# tiny_tht_encoder_board.net
KiCad netlist of a schematic drawn in EAGLE
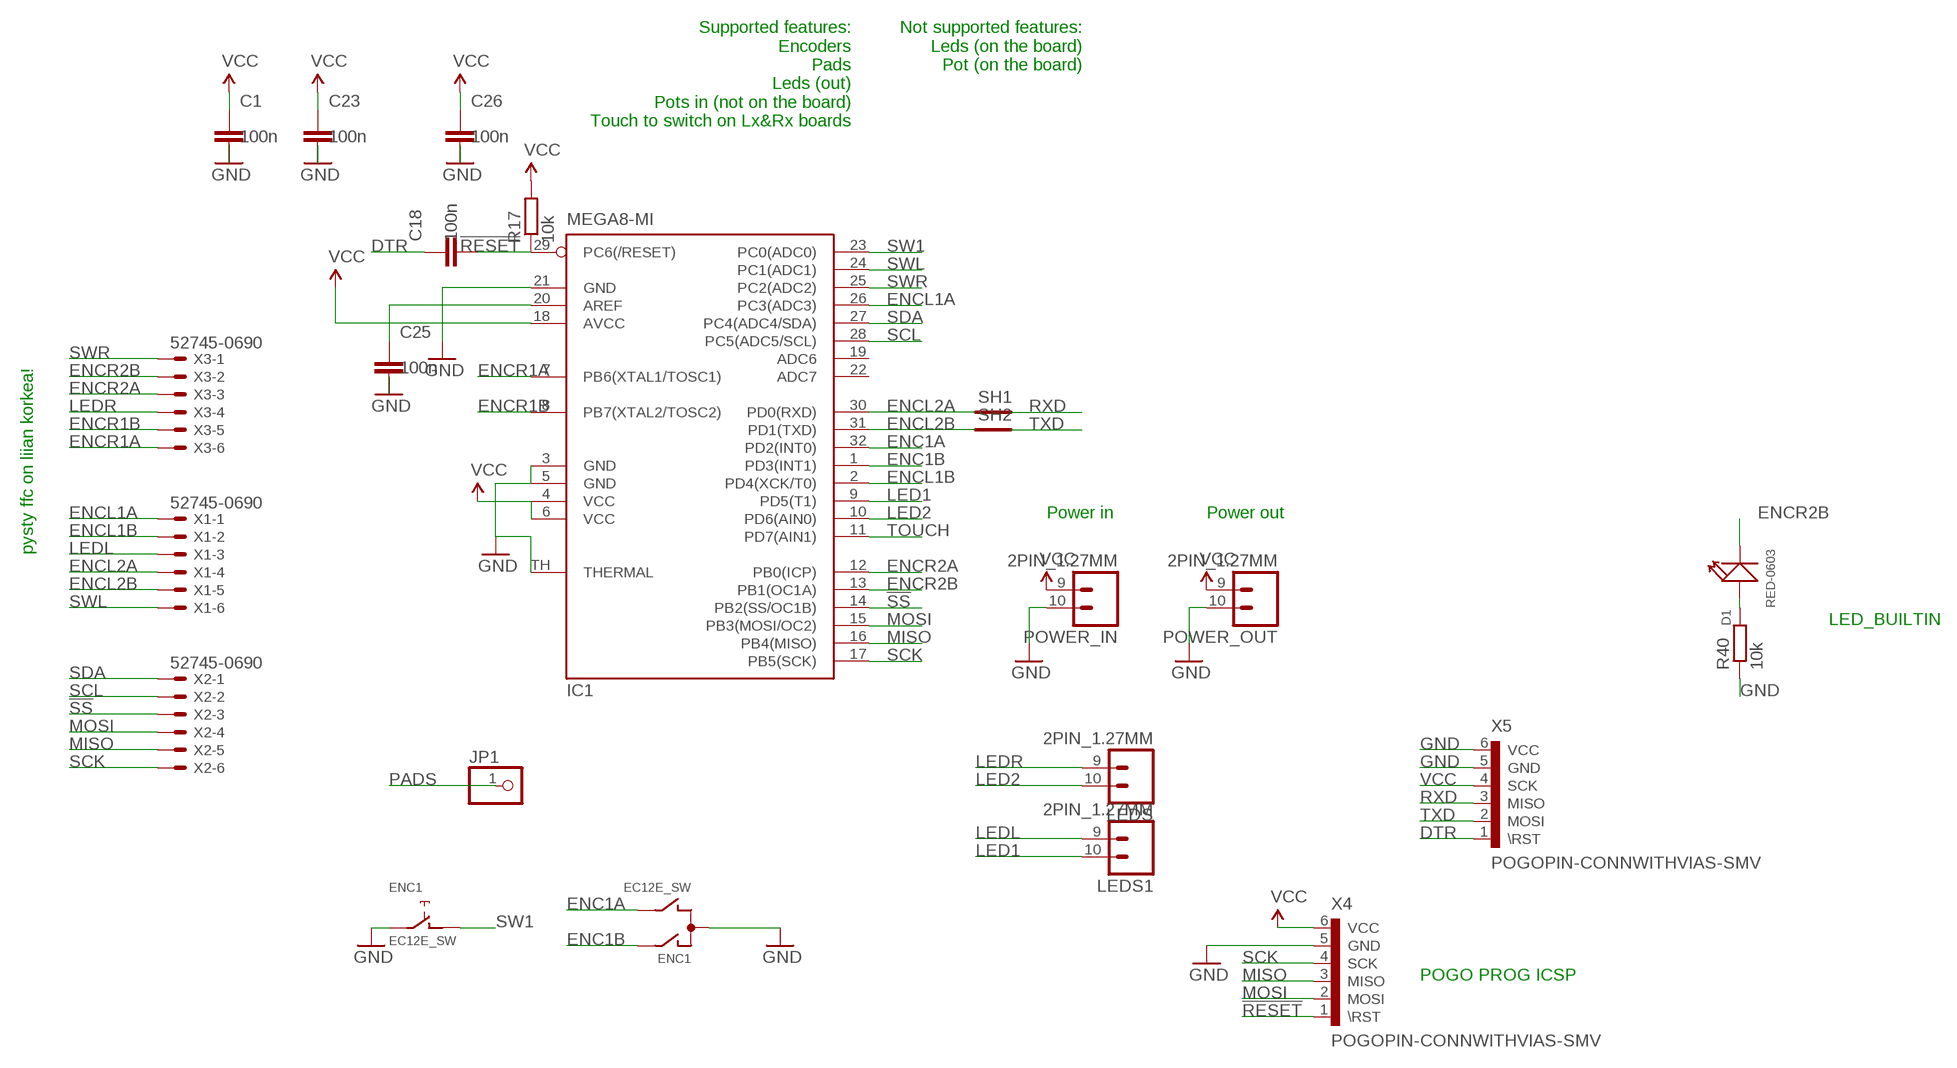
[diagram p0: schematic, sheet 1]
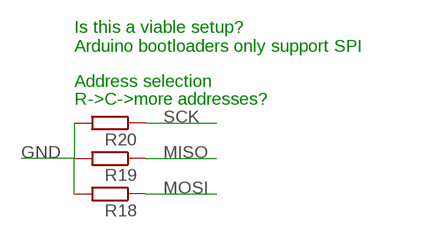
[diagram p1: schematic, sheet 2]
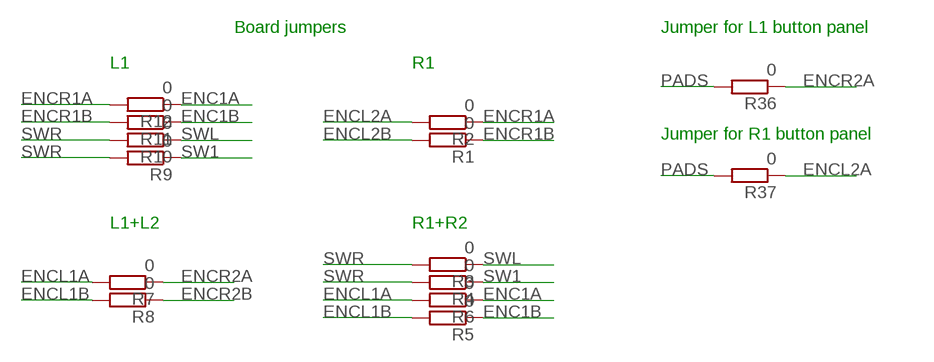
[diagram p2: schematic, sheet 3]

(export (version "E")
  (design (tool "Eeschema 10.0.6"))
  (components
    (comp (ref "R1")
      (value "0")
      (footprint "eagle-import:R0603")
      (fields (field (name "SPICEPREFIX") "R"))
      (libsource (lib "eagle-import") (part "R-EU_R0603"))
    )
    (comp (ref "R2")
      (value "0")
      (footprint "eagle-import:R0603")
      (fields (field (name "SPICEPREFIX") "R"))
      (libsource (lib "eagle-import") (part "R-EU_R0603"))
    )
    (comp (ref "R3")
      (value "0")
      (footprint "eagle-import:R0603")
      (fields (field (name "SPICEPREFIX") "R"))
      (libsource (lib "eagle-import") (part "R-EU_R0603"))
    )
    (comp (ref "R4")
      (value "0")
      (footprint "eagle-import:R0603")
      (fields (field (name "SPICEPREFIX") "R"))
      (libsource (lib "eagle-import") (part "R-EU_R0603"))
    )
    (comp (ref "R5")
      (value "0")
      (footprint "eagle-import:R0603")
      (fields (field (name "SPICEPREFIX") "R"))
      (libsource (lib "eagle-import") (part "R-EU_R0603"))
    )
    (comp (ref "R6")
      (value "0")
      (footprint "eagle-import:R0603")
      (fields (field (name "SPICEPREFIX") "R"))
      (libsource (lib "eagle-import") (part "R-EU_R0603"))
    )
    (comp (ref "R7")
      (value "0")
      (footprint "eagle-import:R0603")
      (fields (field (name "SPICEPREFIX") "R"))
      (libsource (lib "eagle-import") (part "R-EU_R0603"))
    )
    (comp (ref "R8")
      (value "0")
      (footprint "eagle-import:R0603")
      (fields (field (name "SPICEPREFIX") "R"))
      (libsource (lib "eagle-import") (part "R-EU_R0603"))
    )
    (comp (ref "R9")
      (value "0")
      (footprint "eagle-import:R0603")
      (fields (field (name "SPICEPREFIX") "R"))
      (libsource (lib "eagle-import") (part "R-EU_R0603"))
    )
    (comp (ref "R10")
      (value "0")
      (footprint "eagle-import:R0603")
      (fields (field (name "SPICEPREFIX") "R"))
      (libsource (lib "eagle-import") (part "R-EU_R0603"))
    )
    (comp (ref "R11")
      (value "0")
      (footprint "eagle-import:R0603")
      (fields (field (name "SPICEPREFIX") "R"))
      (libsource (lib "eagle-import") (part "R-EU_R0603"))
    )
    (comp (ref "R12")
      (value "0")
      (footprint "eagle-import:R0603")
      (fields (field (name "SPICEPREFIX") "R"))
      (libsource (lib "eagle-import") (part "R-EU_R0603"))
    )
    (comp (ref "R36")
      (value "0")
      (footprint "eagle-import:R0402")
      (fields (field (name "SPICEPREFIX") "R"))
      (libsource (lib "eagle-import") (part "rcl_334_R-EU_R0402"))
    )
    (comp (ref "R37")
      (value "0")
      (footprint "eagle-import:R0402")
      (fields (field (name "SPICEPREFIX") "R"))
      (libsource (lib "eagle-import") (part "rcl_334_R-EU_R0402"))
    )
    (comp (ref "C1")
      (value "100n")
      (footprint "eagle-import:C0402")
      (libsource (lib "eagle-import") (part "C-EUC0402"))
    )
    (comp (ref "C18")
      (value "100n")
      (footprint "eagle-import:C0402")
      (libsource (lib "eagle-import") (part "C-EUC0402"))
    )
    (comp (ref "C23")
      (value "100n")
      (footprint "eagle-import:C0402")
      (libsource (lib "eagle-import") (part "C-EUC0402"))
    )
    (comp (ref "C25")
      (value "100n")
      (footprint "eagle-import:C0402")
      (libsource (lib "eagle-import") (part "C-EUC0402"))
    )
    (comp (ref "C26")
      (value "100n")
      (footprint "eagle-import:C0402")
      (libsource (lib "eagle-import") (part "C-EUC0402"))
    )
    (comp (ref "D1")
      (value "RED-0603")
      (footprint "eagle-import:LED-0603")
      (fields (field (name "MPN") "19-217-R6C-AL1M2VY-3T"))
      (libsource (lib "eagle-import") (part "LED-SMD-RED-DIFFUSED(0603)"))
    )
    (comp (ref "ENC1")
      (value "EC12E_SW")
      (footprint "eagle-import:ALPS_EC12E_SW")
      (fields (field (name "MPN") "EC12E2424407"))
      (libsource (lib "eagle-import") (part "EC12E_SW"))
    )
    (comp (ref "IC1")
      (value "MEGA8-MI")
      (footprint "eagle-import:MLF32-TH")
      (fields (field (name "MPN") "ATMEGA88PA-MU"))
      (libsource (lib "eagle-import") (part "MEGA8-MI"))
    )
    (comp (ref "JP1")
      (value "PINHD-1X1")
      (footprint "eagle-import:1X01")
      (libsource (lib "eagle-import") (part "PINHD-1X1"))
    )
    (comp (ref "LEDS")
      (value "2PIN_1.27MM")
      (footprint "eagle-import:1X02_1.27MM_NO_SILK")
      (libsource (lib "eagle-import") (part "2PIN_1.27MM"))
    )
    (comp (ref "LEDS1")
      (value "2PIN_1.27MM")
      (footprint "eagle-import:1X02_1.27MM_NO_SILK")
      (libsource (lib "eagle-import") (part "2PIN_1.27MM"))
    )
    (comp (ref "POWER_IN")
      (value "2PIN_1.27MM")
      (footprint "eagle-import:1X02_1.27MM_NO_SILK")
      (libsource (lib "eagle-import") (part "2PIN_1.27MM"))
    )
    (comp (ref "POWER_OUT")
      (value "2PIN_1.27MM")
      (footprint "eagle-import:1X02_1.27MM_NO_SILK")
      (libsource (lib "eagle-import") (part "2PIN_1.27MM"))
    )
    (comp (ref "R17")
      (value "10k")
      (footprint "eagle-import:R0402")
      (libsource (lib "eagle-import") (part "rcl_334_R-EU_R0402"))
    )
    (comp (ref "R40")
      (value "10k")
      (footprint "eagle-import:R0402")
      (libsource (lib "eagle-import") (part "rcl_334_R-EU_R0402"))
    )
    (comp (ref "SH1")
      (value "SHORT")
      (footprint "eagle-import:SHORT_TOP_8MIL")
      (libsource (lib "eagle-import") (part "SHORT"))
    )
    (comp (ref "SH2")
      (value "SHORT")
      (footprint "eagle-import:SHORT_TOP_8MIL")
      (libsource (lib "eagle-import") (part "SHORT"))
    )
    (comp (ref "X1")
      (value "52745-0690")
      (footprint "eagle-import:52745-0690")
      (fields (field (name "MF") "MOLEX"))
      (libsource (lib "eagle-import") (part "52745-0690"))
    )
    (comp (ref "X2")
      (value "52745-0690")
      (footprint "eagle-import:52745-0690")
      (fields (field (name "MF") "MOLEX"))
      (libsource (lib "eagle-import") (part "52745-0690"))
    )
    (comp (ref "X3")
      (value "52745-0690")
      (footprint "eagle-import:52745-0690")
      (fields (field (name "MF") "MOLEX"))
      (libsource (lib "eagle-import") (part "52745-0690"))
    )
    (comp (ref "X4")
      (value "POGOPIN-CONNWITHVIAS-SMV")
      (footprint "eagle-import:POGOPROG-CONN-OH-SMALLERVIAS")
      (libsource (lib "eagle-import") (part "POGOPIN-CONNWITHVIAS-SMV"))
    )
    (comp (ref "X5")
      (value "POGOPIN-CONNWITHVIAS-SMV")
      (footprint "eagle-import:POGOPROG-CONN-OH-SMALLERVIAS")
      (libsource (lib "eagle-import") (part "POGOPIN-CONNWITHVIAS-SMV"))
    )
    (comp (ref "R18")
      (value "R-EU_R0402")
      (footprint "eagle-import:R0402")
      (libsource (lib "eagle-import") (part "rcl_334_R-EU_R0402"))
    )
    (comp (ref "R19")
      (value "R-EU_R0402")
      (footprint "eagle-import:R0402")
      (libsource (lib "eagle-import") (part "rcl_334_R-EU_R0402"))
    )
    (comp (ref "R20")
      (value "R-EU_R0402")
      (footprint "eagle-import:R0402")
      (libsource (lib "eagle-import") (part "rcl_334_R-EU_R0402"))
    )
  )
  (nets
    (net (code "1") (name "DTR") (class "Default")
      (node (ref "C18") (pin "1") (pinfunction "1_1") (pintype "passive"))
      (node (ref "X5") (pin "1") (pinfunction "\\RST_1") (pintype "bidirectional"))
    )
    (net (code "2") (name "ENC1A") (class "Default")
      (node (ref "ENC1") (pin "B") (pinfunction "B_B") (pintype "passive"))
      (node (ref "IC1") (pin "32") (pinfunction "PD2(INT0)_32") (pintype "bidirectional"))
      (node (ref "R12") (pin "1") (pinfunction "1_1") (pintype "passive"))
      (node (ref "R6") (pin "1") (pinfunction "1_1") (pintype "passive"))
    )
    (net (code "3") (name "ENC1B") (class "Default")
      (node (ref "ENC1") (pin "A") (pinfunction "A_A") (pintype "passive"))
      (node (ref "IC1") (pin "1") (pinfunction "PD3(INT1)_1") (pintype "bidirectional"))
      (node (ref "R11") (pin "1") (pinfunction "1_1") (pintype "passive"))
      (node (ref "R5") (pin "1") (pinfunction "1_1") (pintype "passive"))
    )
    (net (code "4") (name "ENCL1A") (class "Default")
      (node (ref "IC1") (pin "26") (pinfunction "PC3(ADC3)_26") (pintype "bidirectional"))
      (node (ref "R6") (pin "2") (pinfunction "2_2") (pintype "passive"))
      (node (ref "R7") (pin "2") (pinfunction "2_2") (pintype "passive"))
      (node (ref "X1") (pin "1") (pinfunction "S_1") (pintype "passive"))
    )
    (net (code "5") (name "ENCL1B") (class "Default")
      (node (ref "IC1") (pin "2") (pinfunction "PD4(XCK/T0)_2") (pintype "bidirectional"))
      (node (ref "R5") (pin "2") (pinfunction "2_2") (pintype "passive"))
      (node (ref "R8") (pin "2") (pinfunction "2_2") (pintype "passive"))
      (node (ref "X1") (pin "2") (pinfunction "S_2") (pintype "passive"))
    )
    (net (code "6") (name "ENCL2A") (class "Default")
      (node (ref "IC1") (pin "30") (pinfunction "PD0(RXD)_30") (pintype "bidirectional"))
      (node (ref "R2") (pin "2") (pinfunction "2_2") (pintype "passive"))
      (node (ref "R37") (pin "1") (pinfunction "1_1") (pintype "passive"))
      (node (ref "SH1") (pin "P$1") (pinfunction "P$1_P$1") (pintype "bidirectional"))
      (node (ref "X1") (pin "4") (pinfunction "S_4") (pintype "passive"))
    )
    (net (code "7") (name "ENCL2B") (class "Default")
      (node (ref "IC1") (pin "31") (pinfunction "PD1(TXD)_31") (pintype "bidirectional"))
      (node (ref "R1") (pin "2") (pinfunction "2_2") (pintype "passive"))
      (node (ref "SH2") (pin "P$1") (pinfunction "P$1_P$1") (pintype "bidirectional"))
      (node (ref "X1") (pin "5") (pinfunction "S_5") (pintype "passive"))
    )
    (net (code "8") (name "ENCR1A") (class "Default")
      (node (ref "IC1") (pin "7") (pinfunction "PB6(XTAL1/TOSC1)_7") (pintype "bidirectional"))
      (node (ref "R12") (pin "2") (pinfunction "2_2") (pintype "passive"))
      (node (ref "R2") (pin "1") (pinfunction "1_1") (pintype "passive"))
      (node (ref "X3") (pin "6") (pinfunction "S_6") (pintype "passive"))
    )
    (net (code "9") (name "ENCR1B") (class "Default")
      (node (ref "IC1") (pin "8") (pinfunction "PB7(XTAL2/TOSC2)_8") (pintype "bidirectional"))
      (node (ref "R1") (pin "1") (pinfunction "1_1") (pintype "passive"))
      (node (ref "R11") (pin "2") (pinfunction "2_2") (pintype "passive"))
      (node (ref "X3") (pin "5") (pinfunction "S_5") (pintype "passive"))
    )
    (net (code "10") (name "ENCR2A") (class "Default")
      (node (ref "IC1") (pin "12") (pinfunction "PB0(ICP)_12") (pintype "bidirectional"))
      (node (ref "R36") (pin "1") (pinfunction "1_1") (pintype "passive"))
      (node (ref "R7") (pin "1") (pinfunction "1_1") (pintype "passive"))
      (node (ref "X3") (pin "3") (pinfunction "S_3") (pintype "passive"))
    )
    (net (code "11") (name "ENCR2B") (class "Default")
      (node (ref "D1") (pin "-") (pinfunction "-_-") (pintype "passive"))
      (node (ref "IC1") (pin "13") (pinfunction "PB1(OC1A)_13") (pintype "bidirectional"))
      (node (ref "R8") (pin "1") (pinfunction "1_1") (pintype "passive"))
      (node (ref "X3") (pin "2") (pinfunction "S_2") (pintype "passive"))
    )
    (net (code "12") (name "GND") (class "Default")
      (node (ref "C1") (pin "2") (pinfunction "2_2") (pintype "passive"))
      (node (ref "C23") (pin "2") (pinfunction "2_2") (pintype "passive"))
      (node (ref "C25") (pin "2") (pinfunction "2_2") (pintype "passive"))
      (node (ref "C26") (pin "2") (pinfunction "2_2") (pintype "passive"))
      (node (ref "ENC1") (pin "C") (pinfunction "C_C") (pintype "passive"))
      (node (ref "ENC1") (pin "E") (pinfunction "2_E") (pintype "passive"))
      (node (ref "IC1") (pin "21") (pinfunction "GND_21") (pintype "power_in"))
      (node (ref "IC1") (pin "3") (pinfunction "GND_3") (pintype "power_in"))
      (node (ref "IC1") (pin "5") (pinfunction "GND_5") (pintype "power_in"))
      (node (ref "IC1") (pin "TH") (pinfunction "THERMAL_TH") (pintype "passive"))
      (node (ref "POWER_IN") (pin "10") (pinfunction "2_10") (pintype "passive"))
      (node (ref "POWER_OUT") (pin "10") (pinfunction "2_10") (pintype "passive"))
      (node (ref "R18") (pin "2") (pinfunction "2_2") (pintype "passive"))
      (node (ref "R19") (pin "2") (pinfunction "2_2") (pintype "passive"))
      (node (ref "R20") (pin "2") (pinfunction "2_2") (pintype "passive"))
      (node (ref "R40") (pin "1") (pinfunction "1_1") (pintype "passive"))
      (node (ref "X4") (pin "5") (pinfunction "GND_5") (pintype "bidirectional"))
      (node (ref "X5") (pin "5") (pinfunction "GND_5") (pintype "bidirectional"))
      (node (ref "X5") (pin "6") (pinfunction "VCC_6") (pintype "bidirectional"))
    )
    (net (code "13") (name "LED1") (class "Default")
      (node (ref "IC1") (pin "9") (pinfunction "PD5(T1)_9") (pintype "bidirectional"))
      (node (ref "LEDS1") (pin "10") (pinfunction "2_10") (pintype "passive"))
    )
    (net (code "14") (name "LED2") (class "Default")
      (node (ref "IC1") (pin "10") (pinfunction "PD6(AIN0)_10") (pintype "bidirectional"))
      (node (ref "LEDS") (pin "10") (pinfunction "2_10") (pintype "passive"))
    )
    (net (code "15") (name "LEDL") (class "Default")
      (node (ref "LEDS1") (pin "9") (pinfunction "1_9") (pintype "passive"))
      (node (ref "X1") (pin "3") (pinfunction "S_3") (pintype "passive"))
    )
    (net (code "16") (name "LEDR") (class "Default")
      (node (ref "LEDS") (pin "9") (pinfunction "1_9") (pintype "passive"))
      (node (ref "X3") (pin "4") (pinfunction "S_4") (pintype "passive"))
    )
    (net (code "17") (name "MISO") (class "Default")
      (node (ref "IC1") (pin "16") (pinfunction "PB4(MISO)_16") (pintype "bidirectional"))
      (node (ref "R19") (pin "1") (pinfunction "1_1") (pintype "passive"))
      (node (ref "X2") (pin "5") (pinfunction "S_5") (pintype "passive"))
      (node (ref "X4") (pin "3") (pinfunction "MISO_3") (pintype "bidirectional"))
    )
    (net (code "18") (name "MOSI") (class "Default")
      (node (ref "IC1") (pin "15") (pinfunction "PB3(MOSI/OC2)_15") (pintype "bidirectional"))
      (node (ref "R18") (pin "1") (pinfunction "1_1") (pintype "passive"))
      (node (ref "X2") (pin "4") (pinfunction "S_4") (pintype "passive"))
      (node (ref "X4") (pin "2") (pinfunction "MOSI_2") (pintype "bidirectional"))
    )
    (net (code "19") (name "Net-(D1-Pad+)") (class "Default")
      (node (ref "D1") (pin "+") (pinfunction "+_+") (pintype "passive"))
      (node (ref "R40") (pin "2") (pinfunction "2_2") (pintype "passive"))
    )
    (net (code "20") (name "Net-(IC1-AREF)") (class "Default")
      (node (ref "C25") (pin "1") (pinfunction "1_1") (pintype "passive"))
      (node (ref "IC1") (pin "20") (pinfunction "AREF_20") (pintype "passive"))
    )
    (net (code "21") (name "PADS") (class "Default")
      (node (ref "JP1") (pin "1") (pinfunction "1_1") (pintype "passive"))
      (node (ref "R36") (pin "2") (pinfunction "2_2") (pintype "passive"))
      (node (ref "R37") (pin "2") (pinfunction "2_2") (pintype "passive"))
    )
    (net (code "22") (name "RXD") (class "Default")
      (node (ref "SH1") (pin "P$2") (pinfunction "P$2_P$2") (pintype "bidirectional"))
      (node (ref "X5") (pin "3") (pinfunction "MISO_3") (pintype "bidirectional"))
    )
    (net (code "23") (name "SCK") (class "Default")
      (node (ref "IC1") (pin "17") (pinfunction "PB5(SCK)_17") (pintype "bidirectional"))
      (node (ref "R20") (pin "1") (pinfunction "1_1") (pintype "passive"))
      (node (ref "X2") (pin "6") (pinfunction "S_6") (pintype "passive"))
      (node (ref "X4") (pin "4") (pinfunction "SCK_4") (pintype "bidirectional"))
    )
    (net (code "24") (name "SCL") (class "Default")
      (node (ref "IC1") (pin "28") (pinfunction "PC5(ADC5/SCL)_28") (pintype "bidirectional"))
      (node (ref "X2") (pin "2") (pinfunction "S_2") (pintype "passive"))
    )
    (net (code "25") (name "SDA") (class "Default")
      (node (ref "IC1") (pin "27") (pinfunction "PC4(ADC4/SDA)_27") (pintype "bidirectional"))
      (node (ref "X2") (pin "1") (pinfunction "S_1") (pintype "passive"))
    )
    (net (code "26") (name "SW1") (class "Default")
      (node (ref "ENC1") (pin "D") (pinfunction "1_D") (pintype "passive"))
      (node (ref "IC1") (pin "23") (pinfunction "PC0(ADC0)_23") (pintype "bidirectional"))
      (node (ref "R4") (pin "1") (pinfunction "1_1") (pintype "passive"))
      (node (ref "R9") (pin "1") (pinfunction "1_1") (pintype "passive"))
    )
    (net (code "27") (name "SWL") (class "Default")
      (node (ref "IC1") (pin "24") (pinfunction "PC1(ADC1)_24") (pintype "bidirectional"))
      (node (ref "R10") (pin "1") (pinfunction "1_1") (pintype "passive"))
      (node (ref "R3") (pin "1") (pinfunction "1_1") (pintype "passive"))
      (node (ref "X1") (pin "6") (pinfunction "S_6") (pintype "passive"))
    )
    (net (code "28") (name "SWR") (class "Default")
      (node (ref "IC1") (pin "25") (pinfunction "PC2(ADC2)_25") (pintype "bidirectional"))
      (node (ref "R10") (pin "2") (pinfunction "2_2") (pintype "passive"))
      (node (ref "R3") (pin "2") (pinfunction "2_2") (pintype "passive"))
      (node (ref "R4") (pin "2") (pinfunction "2_2") (pintype "passive"))
      (node (ref "R9") (pin "2") (pinfunction "2_2") (pintype "passive"))
      (node (ref "X3") (pin "1") (pinfunction "S_1") (pintype "passive"))
    )
    (net (code "29") (name "TOUCH") (class "Default")
      (node (ref "IC1") (pin "11") (pinfunction "PD7(AIN1)_11") (pintype "bidirectional"))
    )
    (net (code "30") (name "TXD") (class "Default")
      (node (ref "SH2") (pin "P$2") (pinfunction "P$2_P$2") (pintype "bidirectional"))
      (node (ref "X5") (pin "2") (pinfunction "MOSI_2") (pintype "bidirectional"))
    )
    (net (code "31") (name "VCC") (class "Default")
      (node (ref "C1") (pin "1") (pinfunction "1_1") (pintype "passive"))
      (node (ref "C23") (pin "1") (pinfunction "1_1") (pintype "passive"))
      (node (ref "C26") (pin "1") (pinfunction "1_1") (pintype "passive"))
      (node (ref "IC1") (pin "18") (pinfunction "AVCC_18") (pintype "power_in"))
      (node (ref "IC1") (pin "4") (pinfunction "VCC_4") (pintype "power_in"))
      (node (ref "IC1") (pin "6") (pinfunction "VCC_6") (pintype "power_in"))
      (node (ref "POWER_IN") (pin "9") (pinfunction "1_9") (pintype "passive"))
      (node (ref "POWER_OUT") (pin "9") (pinfunction "1_9") (pintype "passive"))
      (node (ref "R17") (pin "2") (pinfunction "2_2") (pintype "passive"))
      (node (ref "X4") (pin "6") (pinfunction "VCC_6") (pintype "bidirectional"))
      (node (ref "X5") (pin "4") (pinfunction "SCK_4") (pintype "bidirectional"))
    )
    (net (code "32") (name "unconnected-(IC1-ADC6-Pad19)") (class "Default")
      (node (ref "IC1") (pin "19") (pinfunction "ADC6_19") (pintype "bidirectional"))
    )
    (net (code "33") (name "unconnected-(IC1-ADC7-Pad22)") (class "Default")
      (node (ref "IC1") (pin "22") (pinfunction "ADC7_22") (pintype "bidirectional"))
    )
    (net (code "34") (name "~{RESET}") (class "Default")
      (node (ref "C18") (pin "2") (pinfunction "2_2") (pintype "passive"))
      (node (ref "IC1") (pin "29") (pinfunction "PC6(/RESET)_29") (pintype "bidirectional"))
      (node (ref "R17") (pin "1") (pinfunction "1_1") (pintype "passive"))
      (node (ref "X4") (pin "1") (pinfunction "\\RST_1") (pintype "bidirectional"))
    )
    (net (code "35") (name "~{SS}") (class "Default")
      (node (ref "IC1") (pin "14") (pinfunction "PB2(SS/OC1B)_14") (pintype "bidirectional"))
      (node (ref "X2") (pin "3") (pinfunction "S_3") (pintype "passive"))
    )
  )
)
